# AerO2.net
KiCad netlist of a schematic drawn in Altium Designer
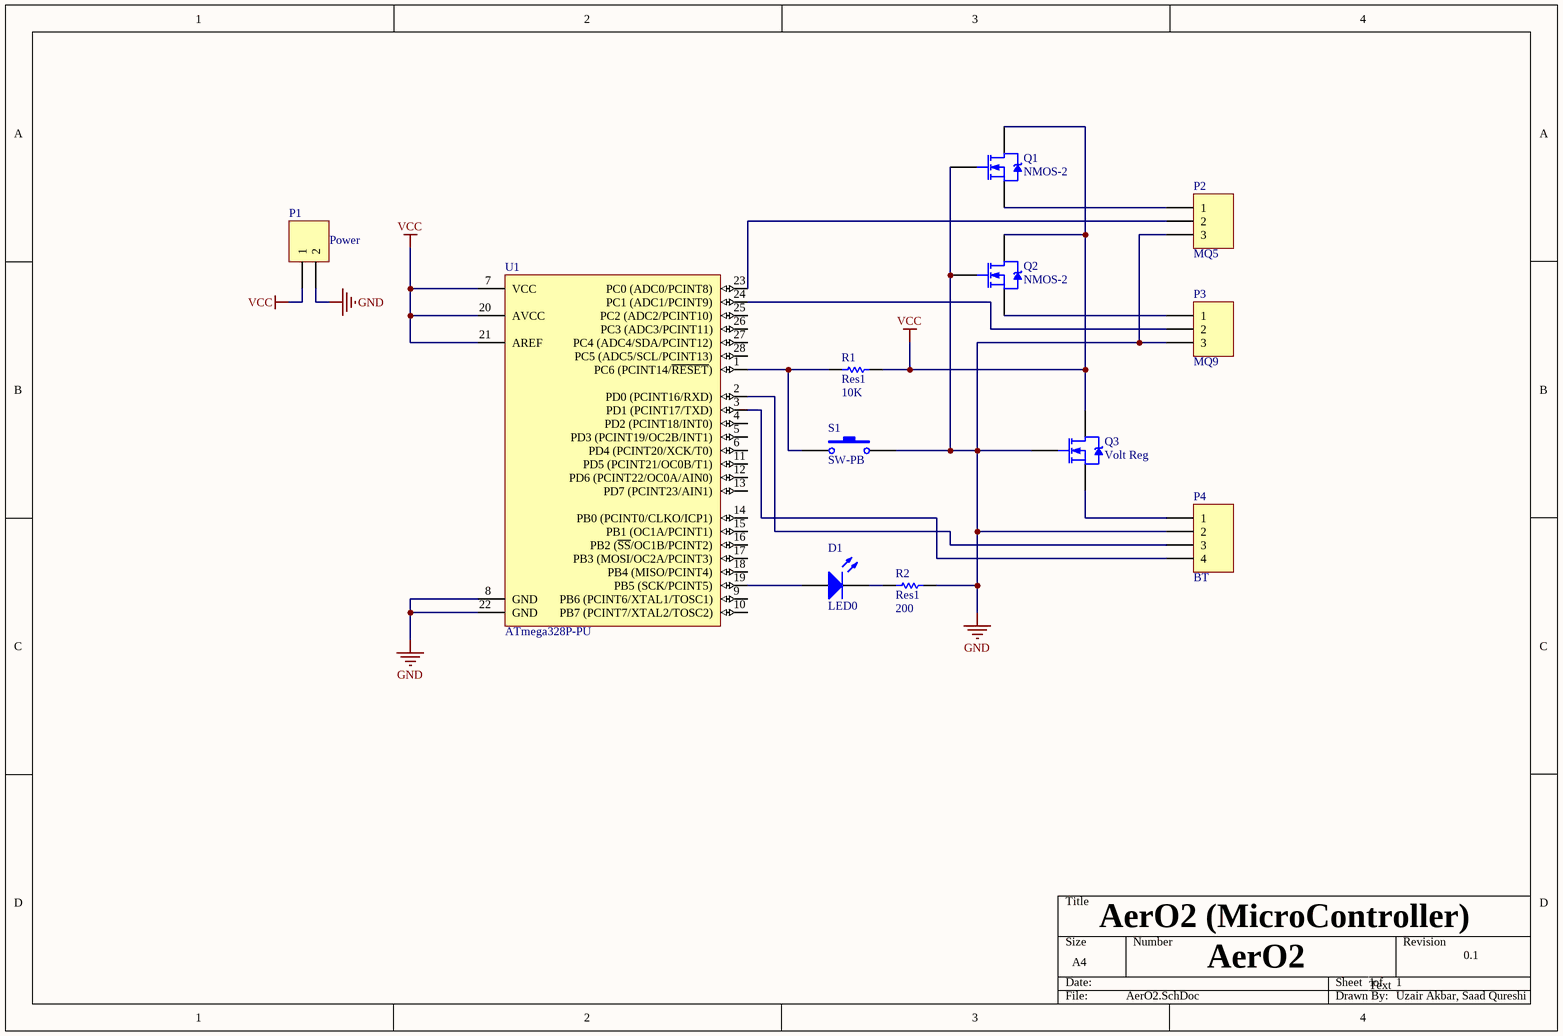
[diagram p0: AerO2.SchDoc]

(export (version "E")
  (design (tool "Eeschema 10.0.6"))
  (components
    (comp (ref "D1")
      (value "LED0")
      (footprint "LED-0")
      (description "Typical INFRARED GaAs LED")
      (fields (field (name "PUBLISHER") "Altium Limited"))
      (libsource (lib "Miscellaneous Devices") (part "LED0"))
    )
    (comp (ref "P1")
      (value "Power")
      (footprint "HDR1X2")
      (description "Header, 2-Pin")
      (fields (field (name "PUBLISHER") "Altium Limited"))
      (libsource (lib "Miscellaneous Connectors") (part "Header 2"))
    )
    (comp (ref "P2")
      (value "MQ5")
      (footprint "HDR1X3")
      (description "Header, 3-Pin")
      (fields (field (name "PUBLISHER") "Altium Limited"))
      (libsource (lib "Miscellaneous Connectors") (part "Header 3"))
    )
    (comp (ref "P3")
      (value "MQ9")
      (footprint "HDR1X3")
      (description "Header, 3-Pin")
      (fields (field (name "PUBLISHER") "Altium Limited"))
      (libsource (lib "Miscellaneous Connectors") (part "Header 3"))
    )
    (comp (ref "P4")
      (value "BT")
      (footprint "HDR1X4")
      (description "Header, 4-Pin")
      (fields (field (name "PUBLISHER") "Altium Limited"))
      (libsource (lib "Miscellaneous Connectors") (part "Header 4"))
    )
    (comp (ref "Q1")
      (value "NMOS-2")
      (footprint "TO-220AB")
      (description "N-Channel Power MOSFET")
      (fields (field (name "PUBLISHER") "Altium Limited"))
      (libsource (lib "Miscellaneous Devices") (part "NMOS-2"))
    )
    (comp (ref "Q2")
      (value "NMOS-2")
      (footprint "TO-220AB")
      (description "N-Channel Power MOSFET")
      (fields (field (name "PUBLISHER") "Altium Limited"))
      (libsource (lib "Miscellaneous Devices") (part "NMOS-2"))
    )
    (comp (ref "Q3")
      (value "Volt Reg")
      (footprint "TO-220AB")
      (description "N-Channel Power MOSFET")
      (fields (field (name "PUBLISHER") "Altium Limited"))
      (libsource (lib "Miscellaneous Devices") (part "NMOS-2"))
    )
    (comp (ref "R1")
      (value "Res1")
      (footprint "AXIAL-0.3")
      (description "Resistor")
      (fields (field (name "ALTIUM_VALUE") "10K") (field (name "PUBLISHER") "Altium Limited"))
      (libsource (lib "Miscellaneous Devices") (part "Res1"))
    )
    (comp (ref "R2")
      (value "Res1")
      (footprint "AXIAL-0.3")
      (description "Resistor")
      (fields (field (name "ALTIUM_VALUE") "200") (field (name "PUBLISHER") "Altium Limited"))
      (libsource (lib "Miscellaneous Devices") (part "Res1"))
    )
    (comp (ref "S1")
      (value "SW-PB")
      (footprint "SPST-2")
      (description "Switch")
      (fields (field (name "PUBLISHER") "Altium Limited"))
      (libsource (lib "Miscellaneous Devices") (part "SW-PB"))
    )
    (comp (ref "U1")
      (value "ATmega328P-PU")
      (footprint "28P3")
      (fields (field (name "PUBLISHER") "Altium Limited"))
      (libsource (lib "Atmel Microcontroller 8-Bit megaAVR") (part "ATmega328P-PU"))
    )
  )
  (nets
    (net (code "1") (name "GND") (class "Default")
      (node (ref "P1") (pin "2") (pinfunction "2_2") (pintype "passive"))
      (node (ref "P2") (pin "3") (pinfunction "3_3") (pintype "passive"))
      (node (ref "P3") (pin "3") (pinfunction "3_3") (pintype "passive"))
      (node (ref "P4") (pin "2") (pinfunction "2_2") (pintype "passive"))
      (node (ref "Q1") (pin "1") (pinfunction "G_1") (pintype "passive"))
      (node (ref "Q2") (pin "1") (pinfunction "G_1") (pintype "passive"))
      (node (ref "Q3") (pin "1") (pinfunction "G_1") (pintype "passive"))
      (node (ref "R2") (pin "2") (pinfunction "2_2") (pintype "passive"))
      (node (ref "S1") (pin "2") (pinfunction "2_2") (pintype "passive"))
      (node (ref "U1") (pin "22") (pinfunction "GND_22") (pintype "power_in"))
      (node (ref "U1") (pin "8") (pinfunction "GND_8") (pintype "power_in"))
    )
    (net (code "2") (name "Net-(D1-A)") (class "Default")
      (node (ref "D1") (pin "1") (pinfunction "A_1") (pintype "passive"))
      (node (ref "U1") (pin "19") (pinfunction "PB5_(SCK/PCINT5)_19") (pintype "bidirectional"))
    )
    (net (code "3") (name "Net-(D1-K)") (class "Default")
      (node (ref "D1") (pin "2") (pinfunction "K_2") (pintype "passive"))
      (node (ref "R2") (pin "1") (pinfunction "1_1") (pintype "passive"))
    )
    (net (code "4") (name "Net-(Q1-S)") (class "Default")
      (node (ref "P2") (pin "1") (pinfunction "1_1") (pintype "passive"))
      (node (ref "Q1") (pin "3") (pinfunction "S_3") (pintype "passive"))
    )
    (net (code "5") (name "Net-(Q2-S)") (class "Default")
      (node (ref "P3") (pin "1") (pinfunction "1_1") (pintype "passive"))
      (node (ref "Q2") (pin "3") (pinfunction "S_3") (pintype "passive"))
    )
    (net (code "6") (name "Net-(Q3-S)") (class "Default")
      (node (ref "P4") (pin "1") (pinfunction "1_1") (pintype "passive"))
      (node (ref "Q3") (pin "3") (pinfunction "S_3") (pintype "passive"))
    )
    (net (code "7") (name "Net-(U1-PC0_(ADC0{slash}PCINT8))") (class "Default")
      (node (ref "P2") (pin "2") (pinfunction "2_2") (pintype "passive"))
      (node (ref "U1") (pin "23") (pinfunction "PC0_(ADC0/PCINT8)_23") (pintype "bidirectional"))
    )
    (net (code "8") (name "Net-(U1-PC1_(ADC1{slash}PCINT9))") (class "Default")
      (node (ref "P3") (pin "2") (pinfunction "2_2") (pintype "passive"))
      (node (ref "U1") (pin "24") (pinfunction "PC1_(ADC1/PCINT9)_24") (pintype "bidirectional"))
    )
    (net (code "9") (name "Net-(U1-PC6_(PCINT14{slash}~{RESET}))") (class "Default")
      (node (ref "R1") (pin "1") (pinfunction "1_1") (pintype "passive"))
      (node (ref "S1") (pin "1") (pinfunction "1_1") (pintype "passive"))
      (node (ref "U1") (pin "1") (pinfunction "PC6_(PCINT14/~{RESET})_1") (pintype "bidirectional"))
    )
    (net (code "10") (name "Net-(U1-PD0_(PCINT16{slash}RXD))") (class "Default")
      (node (ref "P4") (pin "3") (pinfunction "3_3") (pintype "passive"))
      (node (ref "U1") (pin "2") (pinfunction "PD0_(PCINT16/RXD)_2") (pintype "bidirectional"))
    )
    (net (code "11") (name "Net-(U1-PD1_(PCINT17{slash}TXD))") (class "Default")
      (node (ref "P4") (pin "4") (pinfunction "4_4") (pintype "passive"))
      (node (ref "U1") (pin "3") (pinfunction "PD1_(PCINT17/TXD)_3") (pintype "bidirectional"))
    )
    (net (code "12") (name "VCC") (class "Default")
      (node (ref "P1") (pin "1") (pinfunction "1_1") (pintype "passive"))
      (node (ref "Q1") (pin "2") (pinfunction "D_2") (pintype "passive"))
      (node (ref "Q2") (pin "2") (pinfunction "D_2") (pintype "passive"))
      (node (ref "Q3") (pin "2") (pinfunction "D_2") (pintype "passive"))
      (node (ref "R1") (pin "2") (pinfunction "2_2") (pintype "passive"))
      (node (ref "U1") (pin "20") (pinfunction "AVCC_20") (pintype "power_in"))
      (node (ref "U1") (pin "21") (pinfunction "AREF_21") (pintype "power_in"))
      (node (ref "U1") (pin "7") (pinfunction "VCC_7") (pintype "power_in"))
    )
    (net (code "13") (name "unconnected-(U1-PB0_(PCINT0{slash}CLKO{slash}ICP1)-Pad14)") (class "Default")
      (node (ref "U1") (pin "14") (pinfunction "PB0_(PCINT0/CLKO/ICP1)_14") (pintype "bidirectional"))
    )
    (net (code "14") (name "unconnected-(U1-PB1_(OC1A{slash}PCINT1)-Pad15)") (class "Default")
      (node (ref "U1") (pin "15") (pinfunction "PB1_(OC1A/PCINT1)_15") (pintype "bidirectional"))
    )
    (net (code "15") (name "unconnected-(U1-PB2_(~{SS}{slash}OC1B{slash}PCINT2)-Pad16)") (class "Default")
      (node (ref "U1") (pin "16") (pinfunction "PB2_(~{SS}/OC1B/PCINT2)_16") (pintype "bidirectional"))
    )
    (net (code "16") (name "unconnected-(U1-PB3_(MOSI{slash}OC2A{slash}PCINT3)-Pad17)") (class "Default")
      (node (ref "U1") (pin "17") (pinfunction "PB3_(MOSI/OC2A/PCINT3)_17") (pintype "bidirectional"))
    )
    (net (code "17") (name "unconnected-(U1-PB4_(MISO{slash}PCINT4)-Pad18)") (class "Default")
      (node (ref "U1") (pin "18") (pinfunction "PB4_(MISO/PCINT4)_18") (pintype "bidirectional"))
    )
    (net (code "18") (name "unconnected-(U1-PB6_(PCINT6{slash}XTAL1{slash}TOSC1)-Pad9)") (class "Default")
      (node (ref "U1") (pin "9") (pinfunction "PB6_(PCINT6/XTAL1/TOSC1)_9") (pintype "bidirectional"))
    )
    (net (code "19") (name "unconnected-(U1-PB7_(PCINT7{slash}XTAL2{slash}TOSC2)-Pad10)") (class "Default")
      (node (ref "U1") (pin "10") (pinfunction "PB7_(PCINT7/XTAL2/TOSC2)_10") (pintype "bidirectional"))
    )
    (net (code "20") (name "unconnected-(U1-PC2_(ADC2{slash}PCINT10)-Pad25)") (class "Default")
      (node (ref "U1") (pin "25") (pinfunction "PC2_(ADC2/PCINT10)_25") (pintype "bidirectional"))
    )
    (net (code "21") (name "unconnected-(U1-PC3_(ADC3{slash}PCINT11)-Pad26)") (class "Default")
      (node (ref "U1") (pin "26") (pinfunction "PC3_(ADC3/PCINT11)_26") (pintype "bidirectional"))
    )
    (net (code "22") (name "unconnected-(U1-PC4_(ADC4{slash}SDA{slash}PCINT12)-Pad27)") (class "Default")
      (node (ref "U1") (pin "27") (pinfunction "PC4_(ADC4/SDA/PCINT12)_27") (pintype "bidirectional"))
    )
    (net (code "23") (name "unconnected-(U1-PC5_(ADC5{slash}SCL{slash}PCINT13)-Pad28)") (class "Default")
      (node (ref "U1") (pin "28") (pinfunction "PC5_(ADC5/SCL/PCINT13)_28") (pintype "bidirectional"))
    )
    (net (code "24") (name "unconnected-(U1-PD2_(PCINT18{slash}INT0)-Pad4)") (class "Default")
      (node (ref "U1") (pin "4") (pinfunction "PD2_(PCINT18/INT0)_4") (pintype "bidirectional"))
    )
    (net (code "25") (name "unconnected-(U1-PD3_(PCINT19{slash}OC2B{slash}INT1)-Pad5)") (class "Default")
      (node (ref "U1") (pin "5") (pinfunction "PD3_(PCINT19/OC2B/INT1)_5") (pintype "bidirectional"))
    )
    (net (code "26") (name "unconnected-(U1-PD4_(PCINT20{slash}XCK{slash}T0)-Pad6)") (class "Default")
      (node (ref "U1") (pin "6") (pinfunction "PD4_(PCINT20/XCK/T0)_6") (pintype "bidirectional"))
    )
    (net (code "27") (name "unconnected-(U1-PD5_(PCINT21{slash}OC0B{slash}T1)-Pad11)") (class "Default")
      (node (ref "U1") (pin "11") (pinfunction "PD5_(PCINT21/OC0B/T1)_11") (pintype "bidirectional"))
    )
    (net (code "28") (name "unconnected-(U1-PD6_(PCINT22{slash}OC0A{slash}AIN0)-Pad12)") (class "Default")
      (node (ref "U1") (pin "12") (pinfunction "PD6_(PCINT22/OC0A/AIN0)_12") (pintype "bidirectional"))
    )
    (net (code "29") (name "unconnected-(U1-PD7_(PCINT23{slash}AIN1)-Pad13)") (class "Default")
      (node (ref "U1") (pin "13") (pinfunction "PD7_(PCINT23/AIN1)_13") (pintype "bidirectional"))
    )
  )
)
